# MDB.net
KiCad netlist of a schematic drawn in Altium Designer
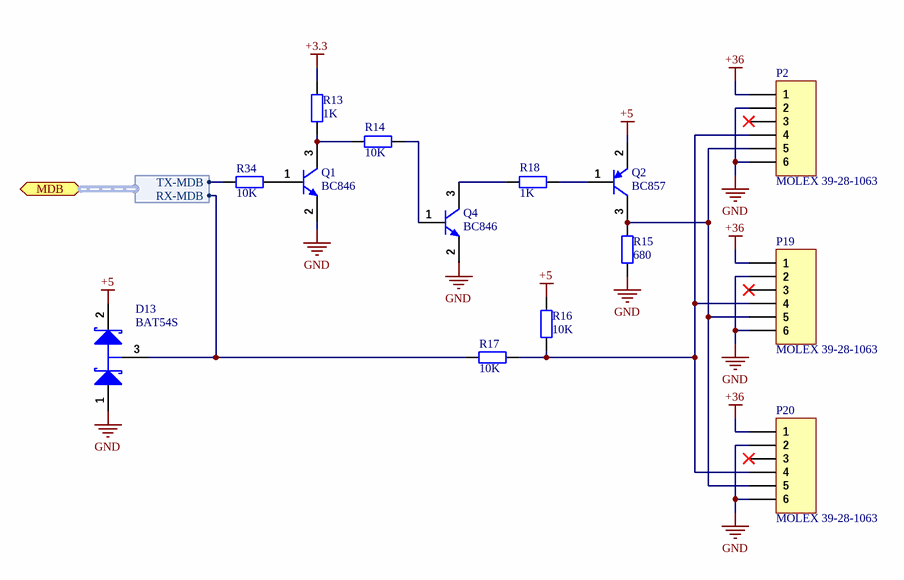
[diagram p0: MDB.SchDoc]

(export (version "E")
  (design (tool "Eeschema 10.0.6"))
  (components
    (comp (ref "D13")
      (value "BAT54S")
      (footprint "SOT23")
      (description "Schottky Barrier Double Diode")
      (fields (field (name "MANUFACTURER") "MULTICOMP"))
      (libsource (lib "Ares") (part "BAT54S"))
    )
    (comp (ref "P2")
      (value "MOLEX 39-28-1063")
      (footprint "MOLEX 39-28-1063")
      (description "Connecteur MDB")
      (fields (field (name "MANUFACTURER") "MOLEX") (field (name "MANUFACTURER PART NUMBER") "39-28-1063"))
      (libsource (lib "Miscellaneous Connectors") (part "Header 6"))
    )
    (comp (ref "P19")
      (value "MOLEX 39-28-1063")
      (footprint "MOLEX 39-28-1063")
      (description "Connecteur MDB")
      (fields (field (name "MANUFACTURER") "MOLEX") (field (name "MANUFACTURER PART NUMBER") "39-28-1063"))
      (libsource (lib "Miscellaneous Connectors") (part "Header 6"))
    )
    (comp (ref "P20")
      (value "MOLEX 39-28-1063")
      (footprint "MOLEX 39-28-1063")
      (description "Connecteur MDB")
      (fields (field (name "MANUFACTURER") "MOLEX") (field (name "MANUFACTURER PART NUMBER") "39-28-1063"))
      (libsource (lib "Miscellaneous Connectors") (part "Header 6"))
    )
    (comp (ref "Q1")
      (value "BC846")
      (footprint "SOT-23")
      (description "NPN General-purpose Transistor")
      (fields (field (name "MANUFACTURER") "NXP"))
      (libsource (lib "Philips Discrete BJT - Low Power") (part "BC846B"))
    )
    (comp (ref "Q2")
      (value "BC857")
      (footprint "SOT-23")
      (description "PNP Switching Transistor")
      (fields (field (name "MANUFACTURER") "NXP"))
      (libsource (lib "Philips Discrete BJT - Low Power") (part "PMBT2907A"))
    )
    (comp (ref "Q4")
      (value "BC846")
      (footprint "SOT-23")
      (description "NPN General-purpose Transistor")
      (fields (field (name "MANUFACTURER") "NXP"))
      (libsource (lib "Philips Discrete BJT - Low Power") (part "BC846B"))
    )
    (comp (ref "R13")
      (value "1K")
      (footprint "R0805")
      (description "Resistor")
      (fields
        (field (name "MANUFACTURER") "MULTICOMP")
        (field (name "MANUFACTURER PART NUMBER") "MC0.1W08051%1KFR")
      )
      (libsource (lib "BRA") (part "Resistor 0805 1K"))
    )
    (comp (ref "R14")
      (value "10K")
      (footprint "R0805")
      (description "Resistor")
      (fields
        (field (name "MANUFACTURER") "MULTICOMP")
        (field (name "MANUFACTURER PART NUMBER") "MC0.1W08051%10KFR")
      )
      (libsource (lib "BRA") (part "Resistor 0805 10K"))
    )
    (comp (ref "R15")
      (value "680")
      (footprint "R0805")
      (description "Resistor")
      (fields
        (field (name "MANUFACTURER") "MULTICOMP")
        (field (name "MANUFACTURER PART NUMBER") "MC01W08051680R")
      )
      (libsource (lib "BRA") (part "Resistor 0805 680"))
    )
    (comp (ref "R16")
      (value "10K")
      (footprint "R0805")
      (description "Resistor")
      (fields
        (field (name "MANUFACTURER") "MULTICOMP")
        (field (name "MANUFACTURER PART NUMBER") "MC0.1W08051%10KFR")
      )
      (libsource (lib "") (part "Resistor 0805 10K_1"))
    )
    (comp (ref "R17")
      (value "10K")
      (footprint "R0805")
      (description "Resistor")
      (fields
        (field (name "MANUFACTURER") "MULTICOMP")
        (field (name "MANUFACTURER PART NUMBER") "MC0.1W08051%10KFR")
      )
      (libsource (lib "BRA") (part "Resistor 0805 10K"))
    )
    (comp (ref "R18")
      (value "1K")
      (footprint "R0805")
      (description "Resistor")
      (fields
        (field (name "MANUFACTURER") "MULTICOMP")
        (field (name "MANUFACTURER PART NUMBER") "MC0.1W08051%1KFR")
      )
      (libsource (lib "") (part "Resistor 0805 1K_1"))
    )
    (comp (ref "R34")
      (value "10K")
      (footprint "R0805")
      (description "Resistor")
      (fields
        (field (name "MANUFACTURER") "MULTICOMP")
        (field (name "MANUFACTURER PART NUMBER") "MC0.1W08051%10KFR")
      )
      (libsource (lib "BRA") (part "Resistor 0805 10K"))
    )
  )
  (nets
    (net (code "2") (name "+3.3") (class "Default")
      (node (ref "R13") (pin "2") (pinfunction "2_2") (pintype "passive"))
    )
    (net (code "3") (name "+5") (class "Default")
      (node (ref "D13") (pin "2") (pinfunction "K_2") (pintype "passive"))
      (node (ref "Q2") (pin "2") (pinfunction "E_2") (pintype "passive"))
      (node (ref "R16") (pin "2") (pinfunction "2_2") (pintype "passive"))
    )
    (net (code "4") (name "+36") (class "Default")
      (node (ref "P19") (pin "1") (pinfunction "1_1") (pintype "passive"))
      (node (ref "P2") (pin "1") (pinfunction "1_1") (pintype "passive"))
      (node (ref "P20") (pin "1") (pinfunction "1_1") (pintype "passive"))
    )
    (net (code "5") (name "/RX-MDB") (class "Default")
      (node (ref "D13") (pin "3") (pinfunction "C_3") (pintype "passive"))
      (node (ref "R17") (pin "2") (pinfunction "2_2") (pintype "passive"))
    )
    (net (code "6") (name "/TX-MDB") (class "Default")
      (node (ref "R34") (pin "2") (pinfunction "2_2") (pintype "passive"))
    )
    (net (code "8") (name "GND") (class "Default")
      (node (ref "D13") (pin "1") (pinfunction "A_1") (pintype "passive"))
      (node (ref "P19") (pin "2") (pinfunction "2_2") (pintype "passive"))
      (node (ref "P19") (pin "6") (pinfunction "6_6") (pintype "passive"))
      (node (ref "P2") (pin "2") (pinfunction "2_2") (pintype "passive"))
      (node (ref "P2") (pin "6") (pinfunction "6_6") (pintype "passive"))
      (node (ref "P20") (pin "2") (pinfunction "2_2") (pintype "passive"))
      (node (ref "P20") (pin "6") (pinfunction "6_6") (pintype "passive"))
      (node (ref "Q1") (pin "2") (pinfunction "E_2") (pintype "passive"))
      (node (ref "Q4") (pin "2") (pinfunction "E_2") (pintype "passive"))
      (node (ref "R15") (pin "1") (pinfunction "1_1") (pintype "passive"))
    )
    (net (code "9") (name "Net-(P19-Pad4)") (class "Default")
      (node (ref "P19") (pin "4") (pinfunction "4_4") (pintype "passive"))
      (node (ref "P2") (pin "4") (pinfunction "4_4") (pintype "passive"))
      (node (ref "P20") (pin "4") (pinfunction "4_4") (pintype "passive"))
      (node (ref "R16") (pin "1") (pinfunction "1_1") (pintype "passive"))
      (node (ref "R17") (pin "1") (pinfunction "1_1") (pintype "passive"))
    )
    (net (code "10") (name "Net-(Q1-B)") (class "Default")
      (node (ref "Q1") (pin "1") (pinfunction "B_1") (pintype "passive"))
      (node (ref "R34") (pin "1") (pinfunction "1_1") (pintype "passive"))
    )
    (net (code "11") (name "Net-(Q1-C)") (class "Default")
      (node (ref "Q1") (pin "3") (pinfunction "C_3") (pintype "passive"))
      (node (ref "R13") (pin "1") (pinfunction "1_1") (pintype "passive"))
      (node (ref "R14") (pin "2") (pinfunction "2_2") (pintype "passive"))
    )
    (net (code "12") (name "Net-(Q2-B)") (class "Default")
      (node (ref "Q2") (pin "1") (pinfunction "B_1") (pintype "passive"))
      (node (ref "R18") (pin "1") (pinfunction "1_1") (pintype "passive"))
    )
    (net (code "13") (name "Net-(Q2-C)") (class "Default")
      (node (ref "P19") (pin "5") (pinfunction "5_5") (pintype "passive"))
      (node (ref "P2") (pin "5") (pinfunction "5_5") (pintype "passive"))
      (node (ref "P20") (pin "5") (pinfunction "5_5") (pintype "passive"))
      (node (ref "Q2") (pin "3") (pinfunction "C_3") (pintype "passive"))
      (node (ref "R15") (pin "2") (pinfunction "2_2") (pintype "passive"))
    )
    (net (code "14") (name "Net-(Q4-B)") (class "Default")
      (node (ref "Q4") (pin "1") (pinfunction "B_1") (pintype "passive"))
      (node (ref "R14") (pin "1") (pinfunction "1_1") (pintype "passive"))
    )
    (net (code "15") (name "Net-(Q4-C)") (class "Default")
      (node (ref "Q4") (pin "3") (pinfunction "C_3") (pintype "passive"))
      (node (ref "R18") (pin "2") (pinfunction "2_2") (pintype "passive"))
    )
    (net (code "16") (name "unconnected-(P2-Pad3)") (class "Default")
      (node (ref "P2") (pin "3") (pinfunction "3_3") (pintype "passive+no_connect"))
    )
    (net (code "17") (name "unconnected-(P19-Pad3)") (class "Default")
      (node (ref "P19") (pin "3") (pinfunction "3_3") (pintype "passive+no_connect"))
    )
    (net (code "18") (name "unconnected-(P20-Pad3)") (class "Default")
      (node (ref "P20") (pin "3") (pinfunction "3_3") (pintype "passive+no_connect"))
    )
  )
)
